# BusPirate-v5_0-SSOP.net
KiCad netlist of a schematic drawn in EAGLE
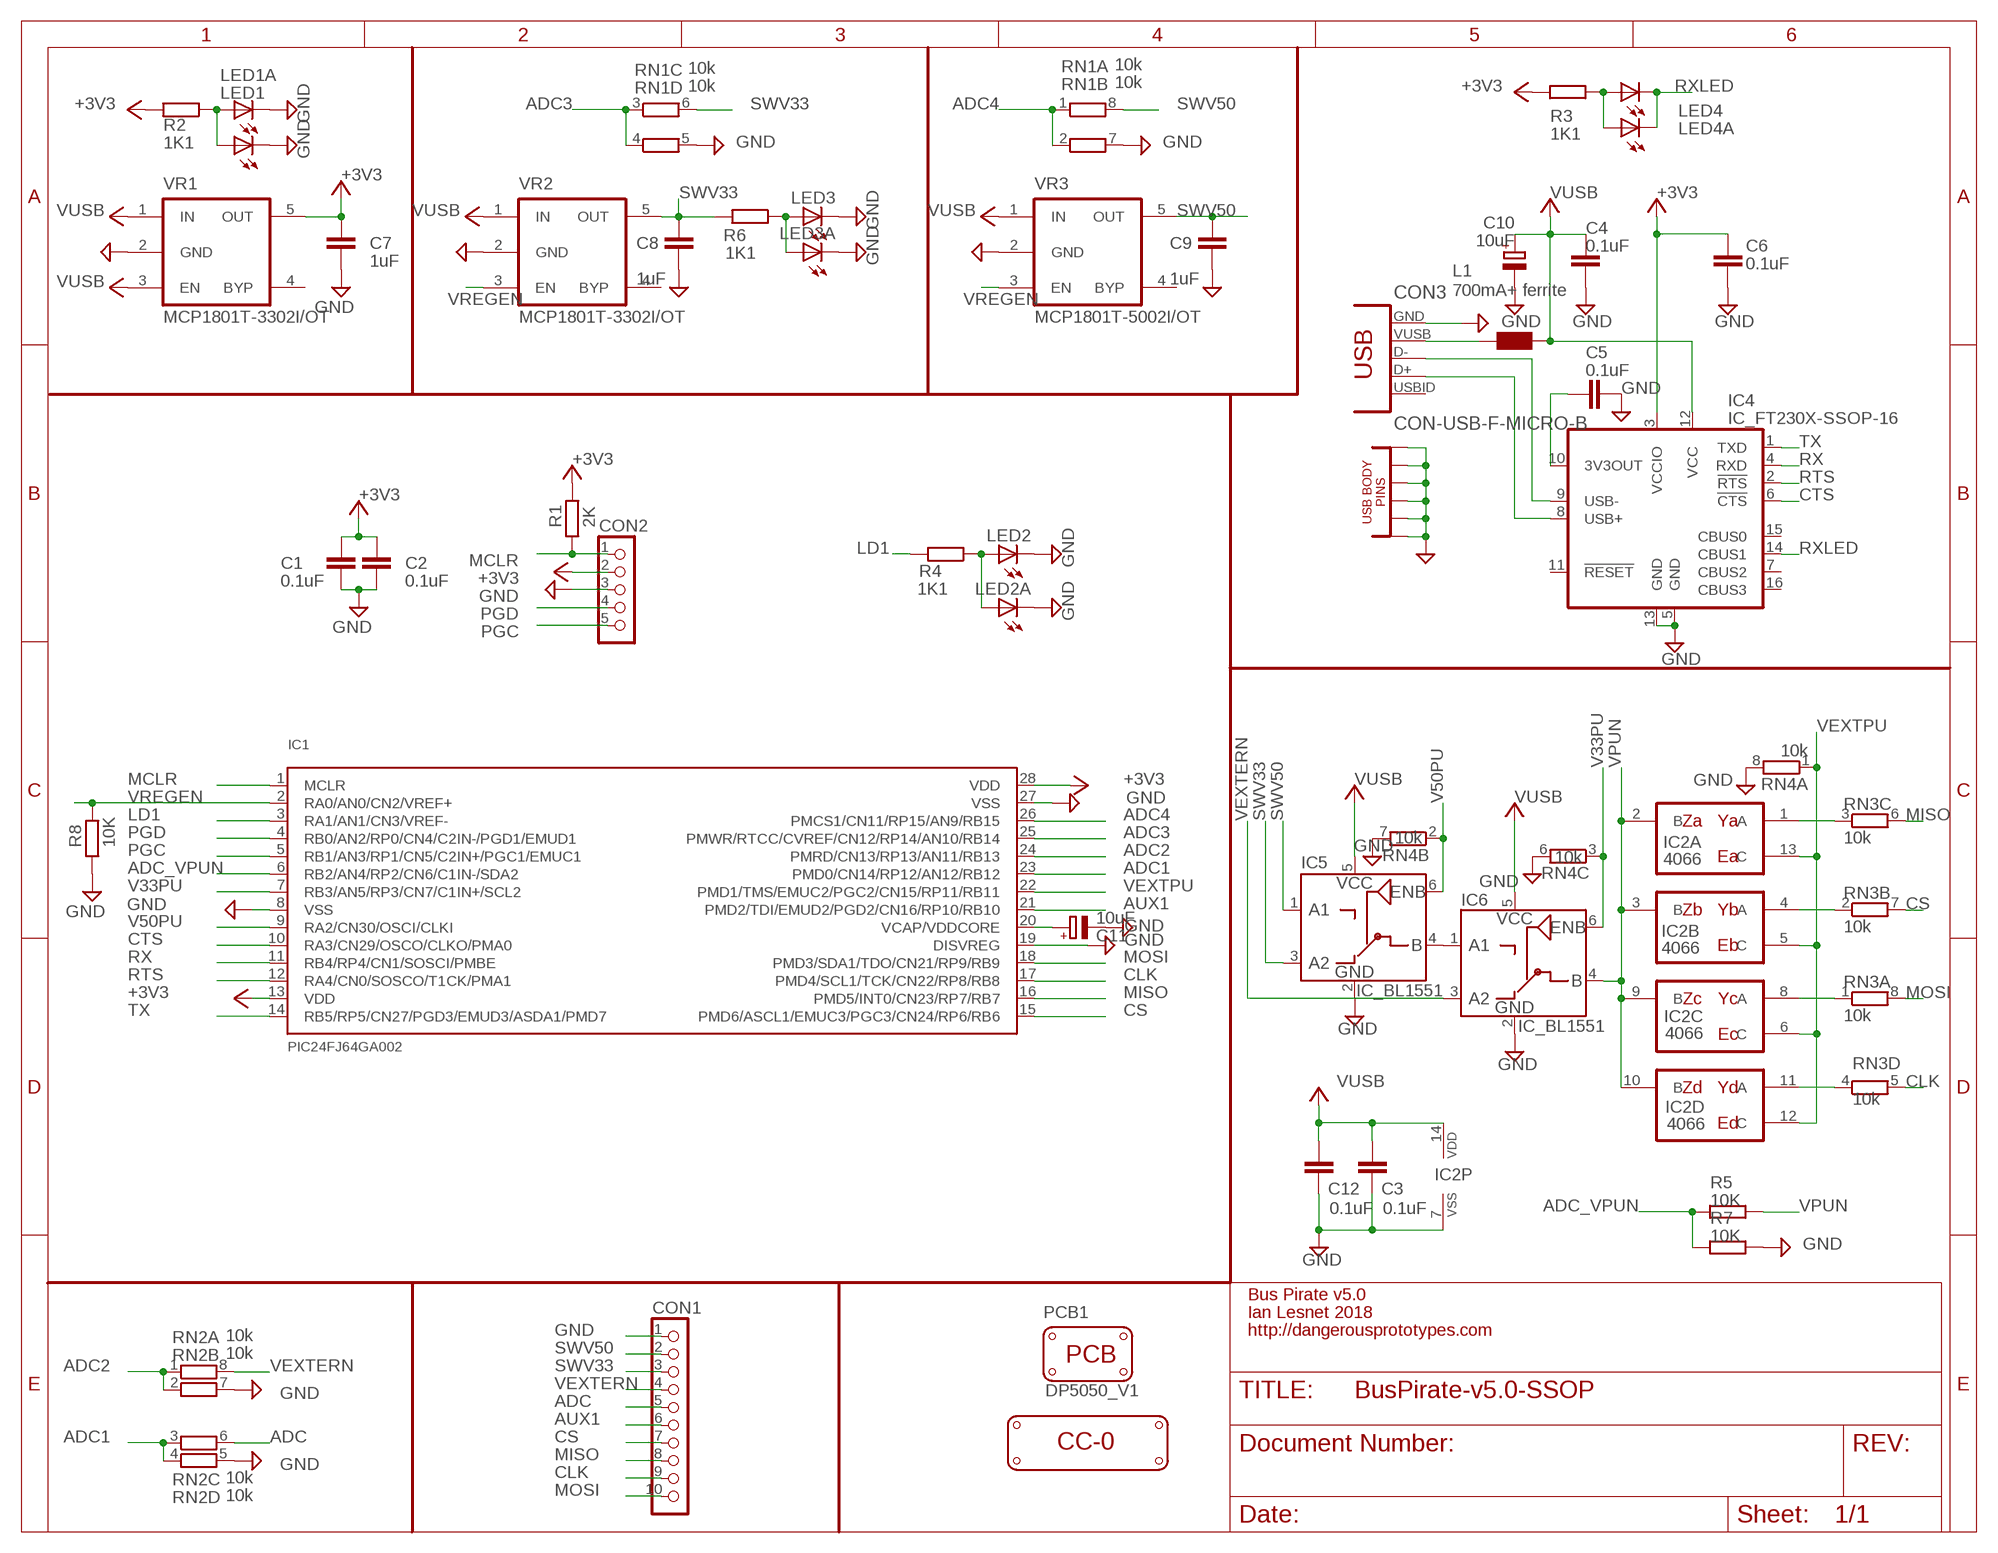
[diagram p0: schematic, sheet 1]

(export (version "E")
  (design (tool "Eeschema 10.0.6"))
  (components
    (comp (ref "C1")
      (value "0.1uF")
      (footprint "eagle-import:C603")
      (libsource (lib "eagle-import") (part "CAPC603"))
    )
    (comp (ref "C2")
      (value "0.1uF")
      (footprint "eagle-import:C603")
      (libsource (lib "eagle-import") (part "CAPC603"))
    )
    (comp (ref "C3")
      (value "0.1uF")
      (footprint "eagle-import:C603")
      (libsource (lib "eagle-import") (part "CAPC603"))
    )
    (comp (ref "C4")
      (value "0.1uF")
      (footprint "eagle-import:C603")
      (libsource (lib "eagle-import") (part "CAPC603"))
    )
    (comp (ref "C5")
      (value "0.1uF")
      (footprint "eagle-import:C603")
      (libsource (lib "eagle-import") (part "CAPC603"))
    )
    (comp (ref "C6")
      (value "0.1uF")
      (footprint "eagle-import:C603")
      (libsource (lib "eagle-import") (part "CAPC603"))
    )
    (comp (ref "C7")
      (value "1uF")
      (footprint "eagle-import:C603")
      (libsource (lib "eagle-import") (part "CAPC603"))
    )
    (comp (ref "C8")
      (value "1uF")
      (footprint "eagle-import:C603")
      (libsource (lib "eagle-import") (part "CAPC603"))
    )
    (comp (ref "C9")
      (value "1uF")
      (footprint "eagle-import:C603")
      (libsource (lib "eagle-import") (part "CAPC603"))
    )
    (comp (ref "C10")
      (value "10uF")
      (footprint "eagle-import:SMC_A")
      (libsource (lib "eagle-import") (part "CPOL-EUSMCA"))
    )
    (comp (ref "C11")
      (value "10uF")
      (footprint "eagle-import:SMC_A")
      (libsource (lib "eagle-import") (part "CPOL-EUSMCA"))
    )
    (comp (ref "C12")
      (value "0.1uF")
      (footprint "eagle-import:C603")
      (libsource (lib "eagle-import") (part "CAPC603"))
    )
    (comp (ref "CON1")
      (value "CON_HEADER_1X10-RIGHT_ANGLED_PTH_SHROUDED")
      (footprint "eagle-import:M1X10_MALE_RIGHT_ANGLES_PTH_SHROUDED")
      (libsource (lib "eagle-import") (part "CON_HEADER_1X10-RIGHT_ANGLED_PTH_SHROUDED"))
    )
    (comp (ref "CON2")
      (value "CON_HEADER_1X05-PTH")
      (footprint "eagle-import:M1X5")
      (libsource (lib "eagle-import") (part "CON_HEADER_1X05-PTH"))
    )
    (comp (ref "CON3")
      (value "CON-USB-F-MICRO-B")
      (footprint "eagle-import:CON_USB_MICRO-B-1-MD05SMXXX-01")
      (libsource (lib "eagle-import") (part "CON-USB-F-MICRO-B"))
    )
    (comp (ref "IC1")
      (value "PIC24FJ64GA002")
      (footprint "eagle-import:SSOP28")
      (libsource (lib "eagle-import") (part "PIC24FJ64GA002"))
    )
    (comp (ref "IC2")
      (value "4066")
      (footprint "eagle-import:TSSOP14")
      (libsource (lib "eagle-import") (part "4066"))
    )
    (comp (ref "IC4")
      (value "IC_FT230X-SSOP-16")
      (footprint "eagle-import:SSOP-16-FTDI")
      (libsource (lib "eagle-import") (part "IC_FT230X-SSOP-16"))
    )
    (comp (ref "IC5")
      (value "IC_BL1551")
      (footprint "eagle-import:SC-70-6")
      (libsource (lib "eagle-import") (part "IC_BL1551"))
    )
    (comp (ref "IC6")
      (value "IC_BL1551")
      (footprint "eagle-import:SC-70-6")
      (libsource (lib "eagle-import") (part "IC_BL1551"))
    )
    (comp (ref "L1")
      (value "700mA+ ferrite")
      (footprint "eagle-import:WE-KI_0805_B")
      (libsource (lib "eagle-import") (part "WE-KIL_0805"))
    )
    (comp (ref "LED1")
      (value "LED-0805")
      (footprint "eagle-import:LED-805")
      (libsource (lib "eagle-import") (part "LED-0805"))
    )
    (comp (ref "LED1A")
      (value "LED-0805")
      (footprint "eagle-import:LED-805")
      (libsource (lib "eagle-import") (part "LED-0805"))
    )
    (comp (ref "LED2")
      (value "LED-0805")
      (footprint "eagle-import:LED-805")
      (libsource (lib "eagle-import") (part "LED-0805"))
    )
    (comp (ref "LED2A")
      (value "LED-0805")
      (footprint "eagle-import:LED-805")
      (libsource (lib "eagle-import") (part "LED-0805"))
    )
    (comp (ref "LED3")
      (value "LED-0805")
      (footprint "eagle-import:LED-805")
      (libsource (lib "eagle-import") (part "LED-0805"))
    )
    (comp (ref "LED3A")
      (value "LED-0805")
      (footprint "eagle-import:LED-805")
      (libsource (lib "eagle-import") (part "LED-0805"))
    )
    (comp (ref "LED4")
      (value "LED-0805")
      (footprint "eagle-import:LED-805")
      (libsource (lib "eagle-import") (part "LED-0805"))
    )
    (comp (ref "LED4A")
      (value "LED-0805")
      (footprint "eagle-import:LED-805")
      (libsource (lib "eagle-import") (part "LED-0805"))
    )
    (comp (ref "LOGO1")
      (value "LOGO_CC-0")
      (footprint "eagle-import:LOGO_CC-0")
      (libsource (lib "eagle-import") (part "LOGO_CC-0"))
    )
    (comp (ref "PCB1")
      (value "PCB_DP_SQUARE-5X5")
      (footprint "eagle-import:DP5050_V1")
      (libsource (lib "eagle-import") (part "PCB_DP_SQUARE-5X5"))
    )
    (comp (ref "R1")
      (value "2K")
      (footprint "eagle-import:R603")
      (libsource (lib "eagle-import") (part "RESISTORR603"))
    )
    (comp (ref "R2")
      (value "1K1")
      (footprint "eagle-import:R603")
      (libsource (lib "eagle-import") (part "RESISTORR603"))
    )
    (comp (ref "R3")
      (value "1K1")
      (footprint "eagle-import:R603")
      (libsource (lib "eagle-import") (part "RESISTORR603"))
    )
    (comp (ref "R4")
      (value "1K1")
      (footprint "eagle-import:R603")
      (libsource (lib "eagle-import") (part "RESISTORR603"))
    )
    (comp (ref "R5")
      (value "10K")
      (footprint "eagle-import:R603")
      (libsource (lib "eagle-import") (part "RESISTORR603"))
    )
    (comp (ref "R6")
      (value "1K1")
      (footprint "eagle-import:R603")
      (libsource (lib "eagle-import") (part "RESISTORR603"))
    )
    (comp (ref "R7")
      (value "10K")
      (footprint "eagle-import:R603")
      (libsource (lib "eagle-import") (part "RESISTORR603"))
    )
    (comp (ref "R8")
      (value "10K")
      (footprint "eagle-import:R603")
      (libsource (lib "eagle-import") (part "RESISTORR603"))
    )
    (comp (ref "RN1")
      (value "10k")
      (footprint "eagle-import:RN8P-4R-CRA06S")
      (libsource (lib "eagle-import") (part "RNETWORK"))
    )
    (comp (ref "RN2")
      (value "10k")
      (footprint "eagle-import:RN8P-4R-CRA06S")
      (libsource (lib "eagle-import") (part "RNETWORK"))
    )
    (comp (ref "RN3")
      (value "10k")
      (footprint "eagle-import:RN8P-4R-CRA06S")
      (libsource (lib "eagle-import") (part "RNETWORK"))
    )
    (comp (ref "RN4")
      (value "10k")
      (footprint "eagle-import:RN8P-4R-CRA06S")
      (libsource (lib "eagle-import") (part "RNETWORK"))
    )
    (comp (ref "VR1")
      (value "MCP1801T-3302I/OT")
      (footprint "eagle-import:SOT-23-5")
      (libsource (lib "eagle-import") (part "MIC5205"))
    )
    (comp (ref "VR2")
      (value "MCP1801T-3302I/OT")
      (footprint "eagle-import:SOT-23-5")
      (libsource (lib "eagle-import") (part "MIC5205"))
    )
    (comp (ref "VR3")
      (value "MCP1801T-5002I/OT")
      (footprint "eagle-import:SOT-23-5")
      (libsource (lib "eagle-import") (part "MIC5205"))
    )
  )
  (nets
    (net (code "1") (name "/ADC") (class "Default")
      (node (ref "CON1") (pin "5") (pinfunction "5_5") (pintype "passive"))
      (node (ref "RN2") (pin "6") (pinfunction "2_6") (pintype "passive"))
    )
    (net (code "2") (name "/ADC1") (class "Default")
      (node (ref "IC1") (pin "23") (pinfunction "PMD0/CN14/RP12/AN12/RB12_23") (pintype "bidirectional"))
      (node (ref "RN2") (pin "3") (pinfunction "1_3") (pintype "passive"))
      (node (ref "RN2") (pin "4") (pinfunction "1_4") (pintype "passive"))
    )
    (net (code "3") (name "/ADC2") (class "Default")
      (node (ref "IC1") (pin "24") (pinfunction "PMRD/CN13/RP13/AN11/RB13_24") (pintype "bidirectional"))
      (node (ref "RN2") (pin "1") (pinfunction "1_1") (pintype "passive"))
      (node (ref "RN2") (pin "2") (pinfunction "1_2") (pintype "passive"))
    )
    (net (code "4") (name "/ADC3") (class "Default")
      (node (ref "IC1") (pin "25") (pinfunction "PMWR/RTCC/CVREF/CN12/RP14/AN10/RB14_25") (pintype "bidirectional"))
      (node (ref "RN1") (pin "3") (pinfunction "1_3") (pintype "passive"))
      (node (ref "RN1") (pin "4") (pinfunction "1_4") (pintype "passive"))
    )
    (net (code "5") (name "/ADC4") (class "Default")
      (node (ref "IC1") (pin "26") (pinfunction "PMCS1/CN11/RP15/AN9/RB15_26") (pintype "bidirectional"))
      (node (ref "RN1") (pin "1") (pinfunction "1_1") (pintype "passive"))
      (node (ref "RN1") (pin "2") (pinfunction "1_2") (pintype "passive"))
    )
    (net (code "6") (name "/ADC_VPUN") (class "Default")
      (node (ref "IC1") (pin "6") (pinfunction "RB2/AN4/RP2/CN6/C1IN-/SDA2_6") (pintype "bidirectional"))
      (node (ref "R5") (pin "2") (pinfunction "2_2") (pintype "passive"))
      (node (ref "R7") (pin "2") (pinfunction "2_2") (pintype "passive"))
    )
    (net (code "7") (name "/AUX1") (class "Default")
      (node (ref "CON1") (pin "6") (pinfunction "6_6") (pintype "passive"))
      (node (ref "IC1") (pin "21") (pinfunction "PMD2/TDI/EMUD2/PGD2/CN16/RP10/RB10_21") (pintype "bidirectional"))
    )
    (net (code "8") (name "/CLK") (class "Default")
      (node (ref "CON1") (pin "9") (pinfunction "9_9") (pintype "passive"))
      (node (ref "IC1") (pin "17") (pinfunction "PMD4/SCL1/TCK/CN22/RP8/RB8_17") (pintype "bidirectional"))
      (node (ref "RN3") (pin "5") (pinfunction "2_5") (pintype "passive"))
    )
    (net (code "9") (name "/CS") (class "Default")
      (node (ref "CON1") (pin "7") (pinfunction "7_7") (pintype "passive"))
      (node (ref "IC1") (pin "15") (pinfunction "PMD6/ASCL1/EMUC3/PGC3/CN24/RP6/RB6_15") (pintype "bidirectional"))
      (node (ref "RN3") (pin "7") (pinfunction "2_7") (pintype "passive"))
    )
    (net (code "10") (name "/CTS") (class "Default")
      (node (ref "IC1") (pin "10") (pinfunction "RA3/CN29/OSCO/CLKO/PMA0_10") (pintype "bidirectional"))
      (node (ref "IC4") (pin "6") (pinfunction "~{CTS}_6") (pintype "bidirectional"))
    )
    (net (code "11") (name "/LD1") (class "Default")
      (node (ref "IC1") (pin "3") (pinfunction "RA1/AN1/CN3/VREF-_3") (pintype "bidirectional"))
      (node (ref "R4") (pin "2") (pinfunction "2_2") (pintype "passive"))
    )
    (net (code "12") (name "/MCLR") (class "Default")
      (node (ref "CON2") (pin "1") (pinfunction "1_1") (pintype "bidirectional"))
      (node (ref "IC1") (pin "1") (pinfunction "MCLR_1") (pintype "input"))
      (node (ref "R1") (pin "1") (pinfunction "1_1") (pintype "passive"))
    )
    (net (code "13") (name "/MISO") (class "Default")
      (node (ref "CON1") (pin "8") (pinfunction "8_8") (pintype "passive"))
      (node (ref "IC1") (pin "16") (pinfunction "PMD5/INT0/CN23/RP7/RB7_16") (pintype "bidirectional"))
      (node (ref "RN3") (pin "6") (pinfunction "2_6") (pintype "passive"))
    )
    (net (code "14") (name "/MOSI") (class "Default")
      (node (ref "CON1") (pin "10") (pinfunction "10_10") (pintype "passive"))
      (node (ref "IC1") (pin "18") (pinfunction "PMD3/SDA1/TDO/CN21/RP9/RB9_18") (pintype "bidirectional"))
      (node (ref "RN3") (pin "8") (pinfunction "2_8") (pintype "passive"))
    )
    (net (code "15") (name "/PGC") (class "Default")
      (node (ref "CON2") (pin "5") (pinfunction "5_5") (pintype "bidirectional"))
      (node (ref "IC1") (pin "5") (pinfunction "RB1/AN3/RP1/CN5/C2IN+/PGC1/EMUC1_5") (pintype "bidirectional"))
    )
    (net (code "16") (name "/PGD") (class "Default")
      (node (ref "CON2") (pin "4") (pinfunction "4_4") (pintype "bidirectional"))
      (node (ref "IC1") (pin "4") (pinfunction "RB0/AN2/RP0/CN4/C2IN-/PGD1/EMUD1_4") (pintype "bidirectional"))
    )
    (net (code "17") (name "/RTS") (class "Default")
      (node (ref "IC1") (pin "12") (pinfunction "RA4/CN0/SOSCO/T1CK/PMA1_12") (pintype "bidirectional"))
      (node (ref "IC4") (pin "2") (pinfunction "~{RTS}_2") (pintype "bidirectional"))
    )
    (net (code "18") (name "/RX") (class "Default")
      (node (ref "IC1") (pin "11") (pinfunction "RB4/RP4/CN1/SOSCI/PMBE_11") (pintype "bidirectional"))
      (node (ref "IC4") (pin "4") (pinfunction "RXD_4") (pintype "input"))
    )
    (net (code "19") (name "/RXLED") (class "Default")
      (node (ref "IC4") (pin "14") (pinfunction "CBUS1_14") (pintype "bidirectional"))
      (node (ref "LED4") (pin "C") (pinfunction "C_C") (pintype "passive"))
      (node (ref "LED4A") (pin "C") (pinfunction "C_C") (pintype "passive"))
    )
    (net (code "20") (name "/SWV33") (class "Default")
      (node (ref "C8") (pin "1") (pinfunction "1_1") (pintype "passive"))
      (node (ref "CON1") (pin "3") (pinfunction "3_3") (pintype "passive"))
      (node (ref "IC5") (pin "3") (pinfunction "A2_3") (pintype "input"))
      (node (ref "R6") (pin "2") (pinfunction "2_2") (pintype "passive"))
      (node (ref "RN1") (pin "6") (pinfunction "2_6") (pintype "passive"))
      (node (ref "VR2") (pin "5") (pinfunction "OUT_5") (pintype "bidirectional"))
    )
    (net (code "21") (name "/SWV50") (class "Default")
      (node (ref "C9") (pin "1") (pinfunction "1_1") (pintype "passive"))
      (node (ref "CON1") (pin "2") (pinfunction "2_2") (pintype "passive"))
      (node (ref "IC5") (pin "1") (pinfunction "A1_1") (pintype "input"))
      (node (ref "RN1") (pin "8") (pinfunction "2_8") (pintype "passive"))
      (node (ref "VR3") (pin "5") (pinfunction "OUT_5") (pintype "bidirectional"))
    )
    (net (code "22") (name "/TX") (class "Default")
      (node (ref "IC1") (pin "14") (pinfunction "RB5/RP5/CN27/PGD3/EMUD3/ASDA1/PMD7_14") (pintype "bidirectional"))
      (node (ref "IC4") (pin "1") (pinfunction "TXD_1") (pintype "output"))
    )
    (net (code "23") (name "/V33PU") (class "Default")
      (node (ref "IC1") (pin "7") (pinfunction "RB3/AN5/RP3/CN7/C1IN+/SCL2_7") (pintype "bidirectional"))
      (node (ref "IC6") (pin "6") (pinfunction "ENB_6") (pintype "input"))
      (node (ref "RN4") (pin "3") (pinfunction "1_3") (pintype "passive"))
    )
    (net (code "24") (name "/V50PU") (class "Default")
      (node (ref "IC1") (pin "9") (pinfunction "RA2/CN30/OSCI/CLKI_9") (pintype "bidirectional"))
      (node (ref "IC5") (pin "6") (pinfunction "ENB_6") (pintype "input"))
      (node (ref "RN4") (pin "2") (pinfunction "1_2") (pintype "passive"))
    )
    (net (code "25") (name "/VEXTERN") (class "Default")
      (node (ref "CON1") (pin "4") (pinfunction "4_4") (pintype "passive"))
      (node (ref "IC6") (pin "3") (pinfunction "A2_3") (pintype "input"))
      (node (ref "RN2") (pin "8") (pinfunction "2_8") (pintype "passive"))
    )
    (net (code "26") (name "/VEXTPU") (class "Default")
      (node (ref "IC1") (pin "22") (pinfunction "PMD1/TMS/EMUC2/PGC2/CN15/RP11/RB11_22") (pintype "bidirectional"))
      (node (ref "IC2") (pin "12") (pinfunction "C_12") (pintype "input"))
      (node (ref "IC2") (pin "13") (pinfunction "C_13") (pintype "input"))
      (node (ref "IC2") (pin "5") (pinfunction "C_5") (pintype "input"))
      (node (ref "IC2") (pin "6") (pinfunction "C_6") (pintype "input"))
      (node (ref "RN4") (pin "1") (pinfunction "1_1") (pintype "passive"))
    )
    (net (code "27") (name "/VPUN") (class "Default")
      (node (ref "IC2") (pin "10") (pinfunction "B_10") (pintype "tri_state"))
      (node (ref "IC2") (pin "2") (pinfunction "B_2") (pintype "tri_state"))
      (node (ref "IC2") (pin "3") (pinfunction "B_3") (pintype "tri_state"))
      (node (ref "IC2") (pin "9") (pinfunction "B_9") (pintype "tri_state"))
      (node (ref "IC6") (pin "4") (pinfunction "B_4") (pintype "output"))
      (node (ref "R5") (pin "1") (pinfunction "1_1") (pintype "passive"))
    )
    (net (code "28") (name "/VREGEN") (class "Default")
      (node (ref "IC1") (pin "2") (pinfunction "RA0/AN0/CN2/VREF+_2") (pintype "bidirectional"))
      (node (ref "R8") (pin "2") (pinfunction "2_2") (pintype "passive"))
      (node (ref "VR2") (pin "3") (pinfunction "EN_3") (pintype "bidirectional"))
      (node (ref "VR3") (pin "3") (pinfunction "EN_3") (pintype "bidirectional"))
    )
    (net (code "29") (name "GND") (class "Default")
      (node (ref "C1") (pin "2") (pinfunction "2_2") (pintype "passive"))
      (node (ref "C10") (pin "-") (pinfunction "-_-") (pintype "passive"))
      (node (ref "C11") (pin "-") (pinfunction "-_-") (pintype "passive"))
      (node (ref "C12") (pin "2") (pinfunction "2_2") (pintype "passive"))
      (node (ref "C2") (pin "2") (pinfunction "2_2") (pintype "passive"))
      (node (ref "C3") (pin "2") (pinfunction "2_2") (pintype "passive"))
      (node (ref "C4") (pin "2") (pinfunction "2_2") (pintype "passive"))
      (node (ref "C5") (pin "2") (pinfunction "2_2") (pintype "passive"))
      (node (ref "C6") (pin "2") (pinfunction "2_2") (pintype "passive"))
      (node (ref "C7") (pin "2") (pinfunction "2_2") (pintype "passive"))
      (node (ref "C8") (pin "2") (pinfunction "2_2") (pintype "passive"))
      (node (ref "C9") (pin "2") (pinfunction "2_2") (pintype "passive"))
      (node (ref "CON1") (pin "1") (pinfunction "1_1") (pintype "passive"))
      (node (ref "CON2") (pin "3") (pinfunction "3_3") (pintype "bidirectional"))
      (node (ref "CON3") (pin "GND1") (pinfunction "P$1_GND1") (pintype "passive"))
      (node (ref "CON3") (pin "GND2") (pinfunction "P$2_GND2") (pintype "passive"))
      (node (ref "CON3") (pin "GND3") (pinfunction "P$3_GND3") (pintype "passive"))
      (node (ref "CON3") (pin "GND4") (pinfunction "P$4_GND4") (pintype "passive"))
      (node (ref "CON3") (pin "GND5") (pinfunction "P$5_GND5") (pintype "passive"))
      (node (ref "CON3") (pin "GND6") (pinfunction "P$6_GND6") (pintype "passive"))
      (node (ref "CON3") (pin "P5") (pinfunction "GND_P5") (pintype "bidirectional"))
      (node (ref "IC1") (pin "19") (pinfunction "DISVREG_19") (pintype "power_in"))
      (node (ref "IC1") (pin "27") (pinfunction "VSS_27") (pintype "power_in"))
      (node (ref "IC1") (pin "8") (pinfunction "VSS_8") (pintype "power_in"))
      (node (ref "IC2") (pin "7") (pinfunction "VSS_7") (pintype "power_in"))
      (node (ref "IC4") (pin "13") (pinfunction "GND_13") (pintype "power_in"))
      (node (ref "IC4") (pin "5") (pinfunction "GND_5") (pintype "power_in"))
      (node (ref "IC5") (pin "2") (pinfunction "GND_2") (pintype "power_in"))
      (node (ref "IC6") (pin "2") (pinfunction "GND_2") (pintype "power_in"))
      (node (ref "LED1") (pin "C") (pinfunction "C_C") (pintype "passive"))
      (node (ref "LED1A") (pin "C") (pinfunction "C_C") (pintype "passive"))
      (node (ref "LED2") (pin "C") (pinfunction "C_C") (pintype "passive"))
      (node (ref "LED2A") (pin "C") (pinfunction "C_C") (pintype "passive"))
      (node (ref "LED3") (pin "C") (pinfunction "C_C") (pintype "passive"))
      (node (ref "LED3A") (pin "C") (pinfunction "C_C") (pintype "passive"))
      (node (ref "R7") (pin "1") (pinfunction "1_1") (pintype "passive"))
      (node (ref "R8") (pin "1") (pinfunction "1_1") (pintype "passive"))
      (node (ref "RN1") (pin "5") (pinfunction "2_5") (pintype "passive"))
      (node (ref "RN1") (pin "7") (pinfunction "2_7") (pintype "passive"))
      (node (ref "RN2") (pin "5") (pinfunction "2_5") (pintype "passive"))
      (node (ref "RN2") (pin "7") (pinfunction "2_7") (pintype "passive"))
      (node (ref "RN4") (pin "6") (pinfunction "2_6") (pintype "passive"))
      (node (ref "RN4") (pin "7") (pinfunction "2_7") (pintype "passive"))
      (node (ref "RN4") (pin "8") (pinfunction "2_8") (pintype "passive"))
      (node (ref "VR1") (pin "2") (pinfunction "GND_2") (pintype "bidirectional"))
      (node (ref "VR2") (pin "2") (pinfunction "GND_2") (pintype "bidirectional"))
      (node (ref "VR3") (pin "2") (pinfunction "GND_2") (pintype "bidirectional"))
    )
    (net (code "30") (name "Net-(CON3A-D+)") (class "Default")
      (node (ref "CON3") (pin "P3") (pinfunction "D+_P3") (pintype "bidirectional"))
      (node (ref "IC4") (pin "8") (pinfunction "USB+_8") (pintype "output"))
    )
    (net (code "31") (name "Net-(CON3A-D-)") (class "Default")
      (node (ref "CON3") (pin "P2") (pinfunction "D-_P2") (pintype "bidirectional"))
      (node (ref "IC4") (pin "9") (pinfunction "USB-_9") (pintype "input"))
    )
    (net (code "32") (name "Net-(CON3A-VUSB)") (class "Default")
      (node (ref "CON3") (pin "P1") (pinfunction "VUSB_P1") (pintype "bidirectional"))
      (node (ref "L1") (pin "2") (pinfunction "1_2") (pintype "passive"))
    )
    (net (code "33") (name "Net-(IC1-VCAP{slash}VDDCORE)") (class "Default")
      (node (ref "C11") (pin "+") (pinfunction "+_+") (pintype "passive"))
      (node (ref "IC1") (pin "20") (pinfunction "VCAP/VDDCORE_20") (pintype "power_in"))
    )
    (net (code "34") (name "Net-(IC2A-A)") (class "Default")
      (node (ref "IC2") (pin "1") (pinfunction "A_1") (pintype "tri_state"))
      (node (ref "RN3") (pin "3") (pinfunction "1_3") (pintype "passive"))
    )
    (net (code "35") (name "Net-(IC2B-A)") (class "Default")
      (node (ref "IC2") (pin "4") (pinfunction "A_4") (pintype "tri_state"))
      (node (ref "RN3") (pin "2") (pinfunction "1_2") (pintype "passive"))
    )
    (net (code "36") (name "Net-(IC2C-A)") (class "Default")
      (node (ref "IC2") (pin "8") (pinfunction "A_8") (pintype "tri_state"))
      (node (ref "RN3") (pin "1") (pinfunction "1_1") (pintype "passive"))
    )
    (net (code "37") (name "Net-(IC2D-A)") (class "Default")
      (node (ref "IC2") (pin "11") (pinfunction "A_11") (pintype "tri_state"))
      (node (ref "RN3") (pin "4") (pinfunction "1_4") (pintype "passive"))
    )
    (net (code "38") (name "Net-(IC4-3V3OUT)") (class "Default")
      (node (ref "C5") (pin "1") (pinfunction "1_1") (pintype "passive"))
      (node (ref "IC4") (pin "10") (pinfunction "3V3OUT_10") (pintype "power_in"))
    )
    (net (code "39") (name "Net-(IC5-B)") (class "Default")
      (node (ref "IC5") (pin "4") (pinfunction "B_4") (pintype "output"))
      (node (ref "IC6") (pin "1") (pinfunction "A1_1") (pintype "input"))
    )
    (net (code "40") (name "Net-(LED1-PadA)") (class "Default")
      (node (ref "LED1") (pin "A") (pinfunction "A_A") (pintype "passive"))
      (node (ref "LED1A") (pin "A") (pinfunction "A_A") (pintype "passive"))
      (node (ref "R2") (pin "1") (pinfunction "1_1") (pintype "passive"))
    )
    (net (code "41") (name "Net-(LED2-PadA)") (class "Default")
      (node (ref "LED2") (pin "A") (pinfunction "A_A") (pintype "passive"))
      (node (ref "LED2A") (pin "A") (pinfunction "A_A") (pintype "passive"))
      (node (ref "R4") (pin "1") (pinfunction "1_1") (pintype "passive"))
    )
    (net (code "42") (name "Net-(LED3-PadA)") (class "Default")
      (node (ref "LED3") (pin "A") (pinfunction "A_A") (pintype "passive"))
      (node (ref "LED3A") (pin "A") (pinfunction "A_A") (pintype "passive"))
      (node (ref "R6") (pin "1") (pinfunction "1_1") (pintype "passive"))
    )
    (net (code "43") (name "Net-(LED4-PadA)") (class "Default")
      (node (ref "LED4") (pin "A") (pinfunction "A_A") (pintype "passive"))
      (node (ref "LED4A") (pin "A") (pinfunction "A_A") (pintype "passive"))
      (node (ref "R3") (pin "1") (pinfunction "1_1") (pintype "passive"))
    )
    (net (code "44") (name "SUPPLY_+3V3") (class "Default")
      (node (ref "C1") (pin "1") (pinfunction "1_1") (pintype "passive"))
      (node (ref "C2") (pin "1") (pinfunction "1_1") (pintype "passive"))
      (node (ref "C6") (pin "1") (pinfunction "1_1") (pintype "passive"))
      (node (ref "C7") (pin "1") (pinfunction "1_1") (pintype "passive"))
      (node (ref "CON2") (pin "2") (pinfunction "2_2") (pintype "bidirectional"))
      (node (ref "IC1") (pin "13") (pinfunction "VDD_13") (pintype "power_in"))
      (node (ref "IC1") (pin "28") (pinfunction "VDD_28") (pintype "power_in"))
      (node (ref "IC4") (pin "3") (pinfunction "VCCIO_3") (pintype "power_in"))
      (node (ref "R1") (pin "2") (pinfunction "2_2") (pintype "passive"))
      (node (ref "R2") (pin "2") (pinfunction "2_2") (pintype "passive"))
      (node (ref "R3") (pin "2") (pinfunction "2_2") (pintype "passive"))
      (node (ref "VR1") (pin "5") (pinfunction "OUT_5") (pintype "bidirectional"))
    )
    (net (code "45") (name "SUPPLY_VUSB") (class "Default")
      (node (ref "C10") (pin "+") (pinfunction "+_+") (pintype "passive"))
      (node (ref "C12") (pin "1") (pinfunction "1_1") (pintype "passive"))
      (node (ref "C3") (pin "1") (pinfunction "1_1") (pintype "passive"))
      (node (ref "C4") (pin "1") (pinfunction "1_1") (pintype "passive"))
      (node (ref "IC2") (pin "14") (pinfunction "VDD_14") (pintype "power_in"))
      (node (ref "IC4") (pin "12") (pinfunction "VCC_12") (pintype "power_in"))
      (node (ref "IC5") (pin "5") (pinfunction "VCC_5") (pintype "power_in"))
      (node (ref "IC6") (pin "5") (pinfunction "VCC_5") (pintype "power_in"))
      (node (ref "L1") (pin "1") (pinfunction "2_1") (pintype "passive"))
      (node (ref "VR1") (pin "1") (pinfunction "IN_1") (pintype "bidirectional"))
      (node (ref "VR1") (pin "3") (pinfunction "EN_3") (pintype "bidirectional"))
      (node (ref "VR2") (pin "1") (pinfunction "IN_1") (pintype "bidirectional"))
      (node (ref "VR3") (pin "1") (pinfunction "IN_1") (pintype "bidirectional"))
    )
    (net (code "46") (name "unconnected-(CON3A-USBID-PadP4)") (class "Default")
      (node (ref "CON3") (pin "P4") (pinfunction "USBID_P4") (pintype "bidirectional"))
    )
    (net (code "47") (name "unconnected-(IC4-CBUS0-Pad15)") (class "Default")
      (node (ref "IC4") (pin "15") (pinfunction "CBUS0_15") (pintype "bidirectional"))
    )
    (net (code "48") (name "unconnected-(IC4-CBUS2-Pad7)") (class "Default")
      (node (ref "IC4") (pin "7") (pinfunction "CBUS2_7") (pintype "bidirectional"))
    )
    (net (code "49") (name "unconnected-(IC4-CBUS3-Pad16)") (class "Default")
      (node (ref "IC4") (pin "16") (pinfunction "CBUS3_16") (pintype "bidirectional"))
    )
    (net (code "50") (name "unconnected-(IC4-~{RESET}-Pad11)") (class "Default")
      (node (ref "IC4") (pin "11") (pinfunction "~{RESET}_11") (pintype "bidirectional"))
    )
    (net (code "51") (name "unconnected-(VR1-BYP-Pad4)") (class "Default")
      (node (ref "VR1") (pin "4") (pinfunction "BYP_4") (pintype "bidirectional"))
    )
    (net (code "52") (name "unconnected-(VR2-BYP-Pad4)") (class "Default")
      (node (ref "VR2") (pin "4") (pinfunction "BYP_4") (pintype "bidirectional"))
    )
    (net (code "53") (name "unconnected-(VR3-BYP-Pad4)") (class "Default")
      (node (ref "VR3") (pin "4") (pinfunction "BYP_4") (pintype "bidirectional"))
    )
  )
)
